# bat-ic-hackon.net
KiCad netlist of a schematic drawn in EAGLE
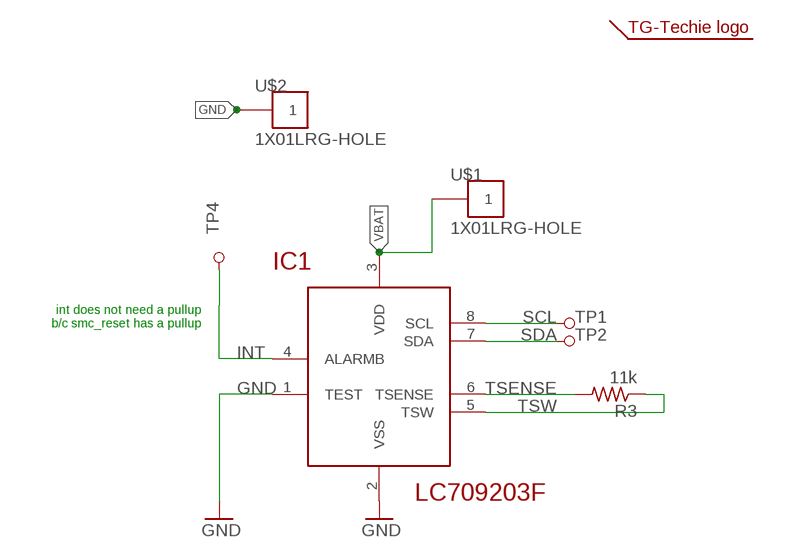
[diagram p0: schematic, sheet 1]

(export (version "E")
  (design (tool "Eeschema 10.0.6"))
  (components
    (comp (ref "IC1")
      (value "LC709203F")
      (footprint "eagle-import:WDFN8_3X4_0.65")
      (libsource (lib "eagle-import") (part "LC709203F"))
    )
    (comp (ref "R3")
      (value "11k")
      (footprint "eagle-import:TG_0402")
      (libsource (lib "eagle-import") (part "R_TG_0402"))
    )
    (comp (ref "TP1")
      (value "TESTPOINT_1X1_SMALL")
      (footprint "eagle-import:1X1_POGO_SMALL")
      (libsource (lib "eagle-import") (part "TESTPOINT_1X1_SMALL"))
    )
    (comp (ref "TP2")
      (value "TESTPOINT_1X1_SMALL")
      (footprint "eagle-import:1X1_POGO_SMALL")
      (libsource (lib "eagle-import") (part "TESTPOINT_1X1_SMALL"))
    )
    (comp (ref "TP4")
      (value "TESTPOINT_1X1_SMALL")
      (footprint "eagle-import:1X1_POGO_SMALL")
      (libsource (lib "eagle-import") (part "TESTPOINT_1X1_SMALL"))
    )
    (comp (ref "U$1")
      (value "1X01LRG-HOLE")
      (footprint "eagle-import:1X1_HOLE_LRG")
      (libsource (lib "eagle-import") (part "1X01LRG-HOLE"))
    )
    (comp (ref "U$2")
      (value "1X01LRG-HOLE")
      (footprint "eagle-import:1X1_HOLE_LRG")
      (libsource (lib "eagle-import") (part "1X01LRG-HOLE"))
    )
    (comp (ref "U$3")
      (value "LOGO-TG-TECHIE5MM-SYMB")
      (footprint "eagle-import:TG-LOGO-5MM-SYMB")
      (libsource (lib "eagle-import") (part "LOGO-TG-TECHIE5MM-SYMB"))
    )
  )
  (nets
    (net (code "1") (name "/INT") (class "Default")
      (node (ref "IC1") (pin "4") (pinfunction "ALARMB_4") (pintype "output"))
      (node (ref "TP4") (pin "1") (pinfunction "P1_1") (pintype "bidirectional"))
    )
    (net (code "2") (name "/SCL") (class "Default")
      (node (ref "IC1") (pin "8") (pinfunction "SCL_8") (pintype "bidirectional"))
      (node (ref "TP1") (pin "1") (pinfunction "P1_1") (pintype "bidirectional"))
    )
    (net (code "3") (name "/SDA") (class "Default")
      (node (ref "IC1") (pin "7") (pinfunction "SDA_7") (pintype "bidirectional"))
      (node (ref "TP2") (pin "1") (pinfunction "P1_1") (pintype "bidirectional"))
    )
    (net (code "4") (name "/TSENSE") (class "Default")
      (node (ref "IC1") (pin "6") (pinfunction "TSENSE_6") (pintype "power_in"))
      (node (ref "R3") (pin "2") (pinfunction "2_2") (pintype "passive"))
    )
    (net (code "5") (name "/TSW") (class "Default")
      (node (ref "IC1") (pin "5") (pinfunction "TSW_5") (pintype "input"))
      (node (ref "R3") (pin "1") (pinfunction "1_1") (pintype "passive"))
    )
    (net (code "6") (name "GND") (class "Default")
      (node (ref "IC1") (pin "1") (pinfunction "TEST_1") (pintype "bidirectional"))
      (node (ref "IC1") (pin "2") (pinfunction "VSS_2") (pintype "power_in"))
      (node (ref "U$2") (pin "1") (pinfunction "1_1") (pintype "bidirectional"))
    )
    (net (code "7") (name "VBAT") (class "Default")
      (node (ref "IC1") (pin "3") (pinfunction "VDD_3") (pintype "power_in"))
      (node (ref "U$1") (pin "1") (pinfunction "1_1") (pintype "bidirectional"))
    )
  )
)
